# UI_measurement.net
KiCad netlist of a schematic drawn in EAGLE
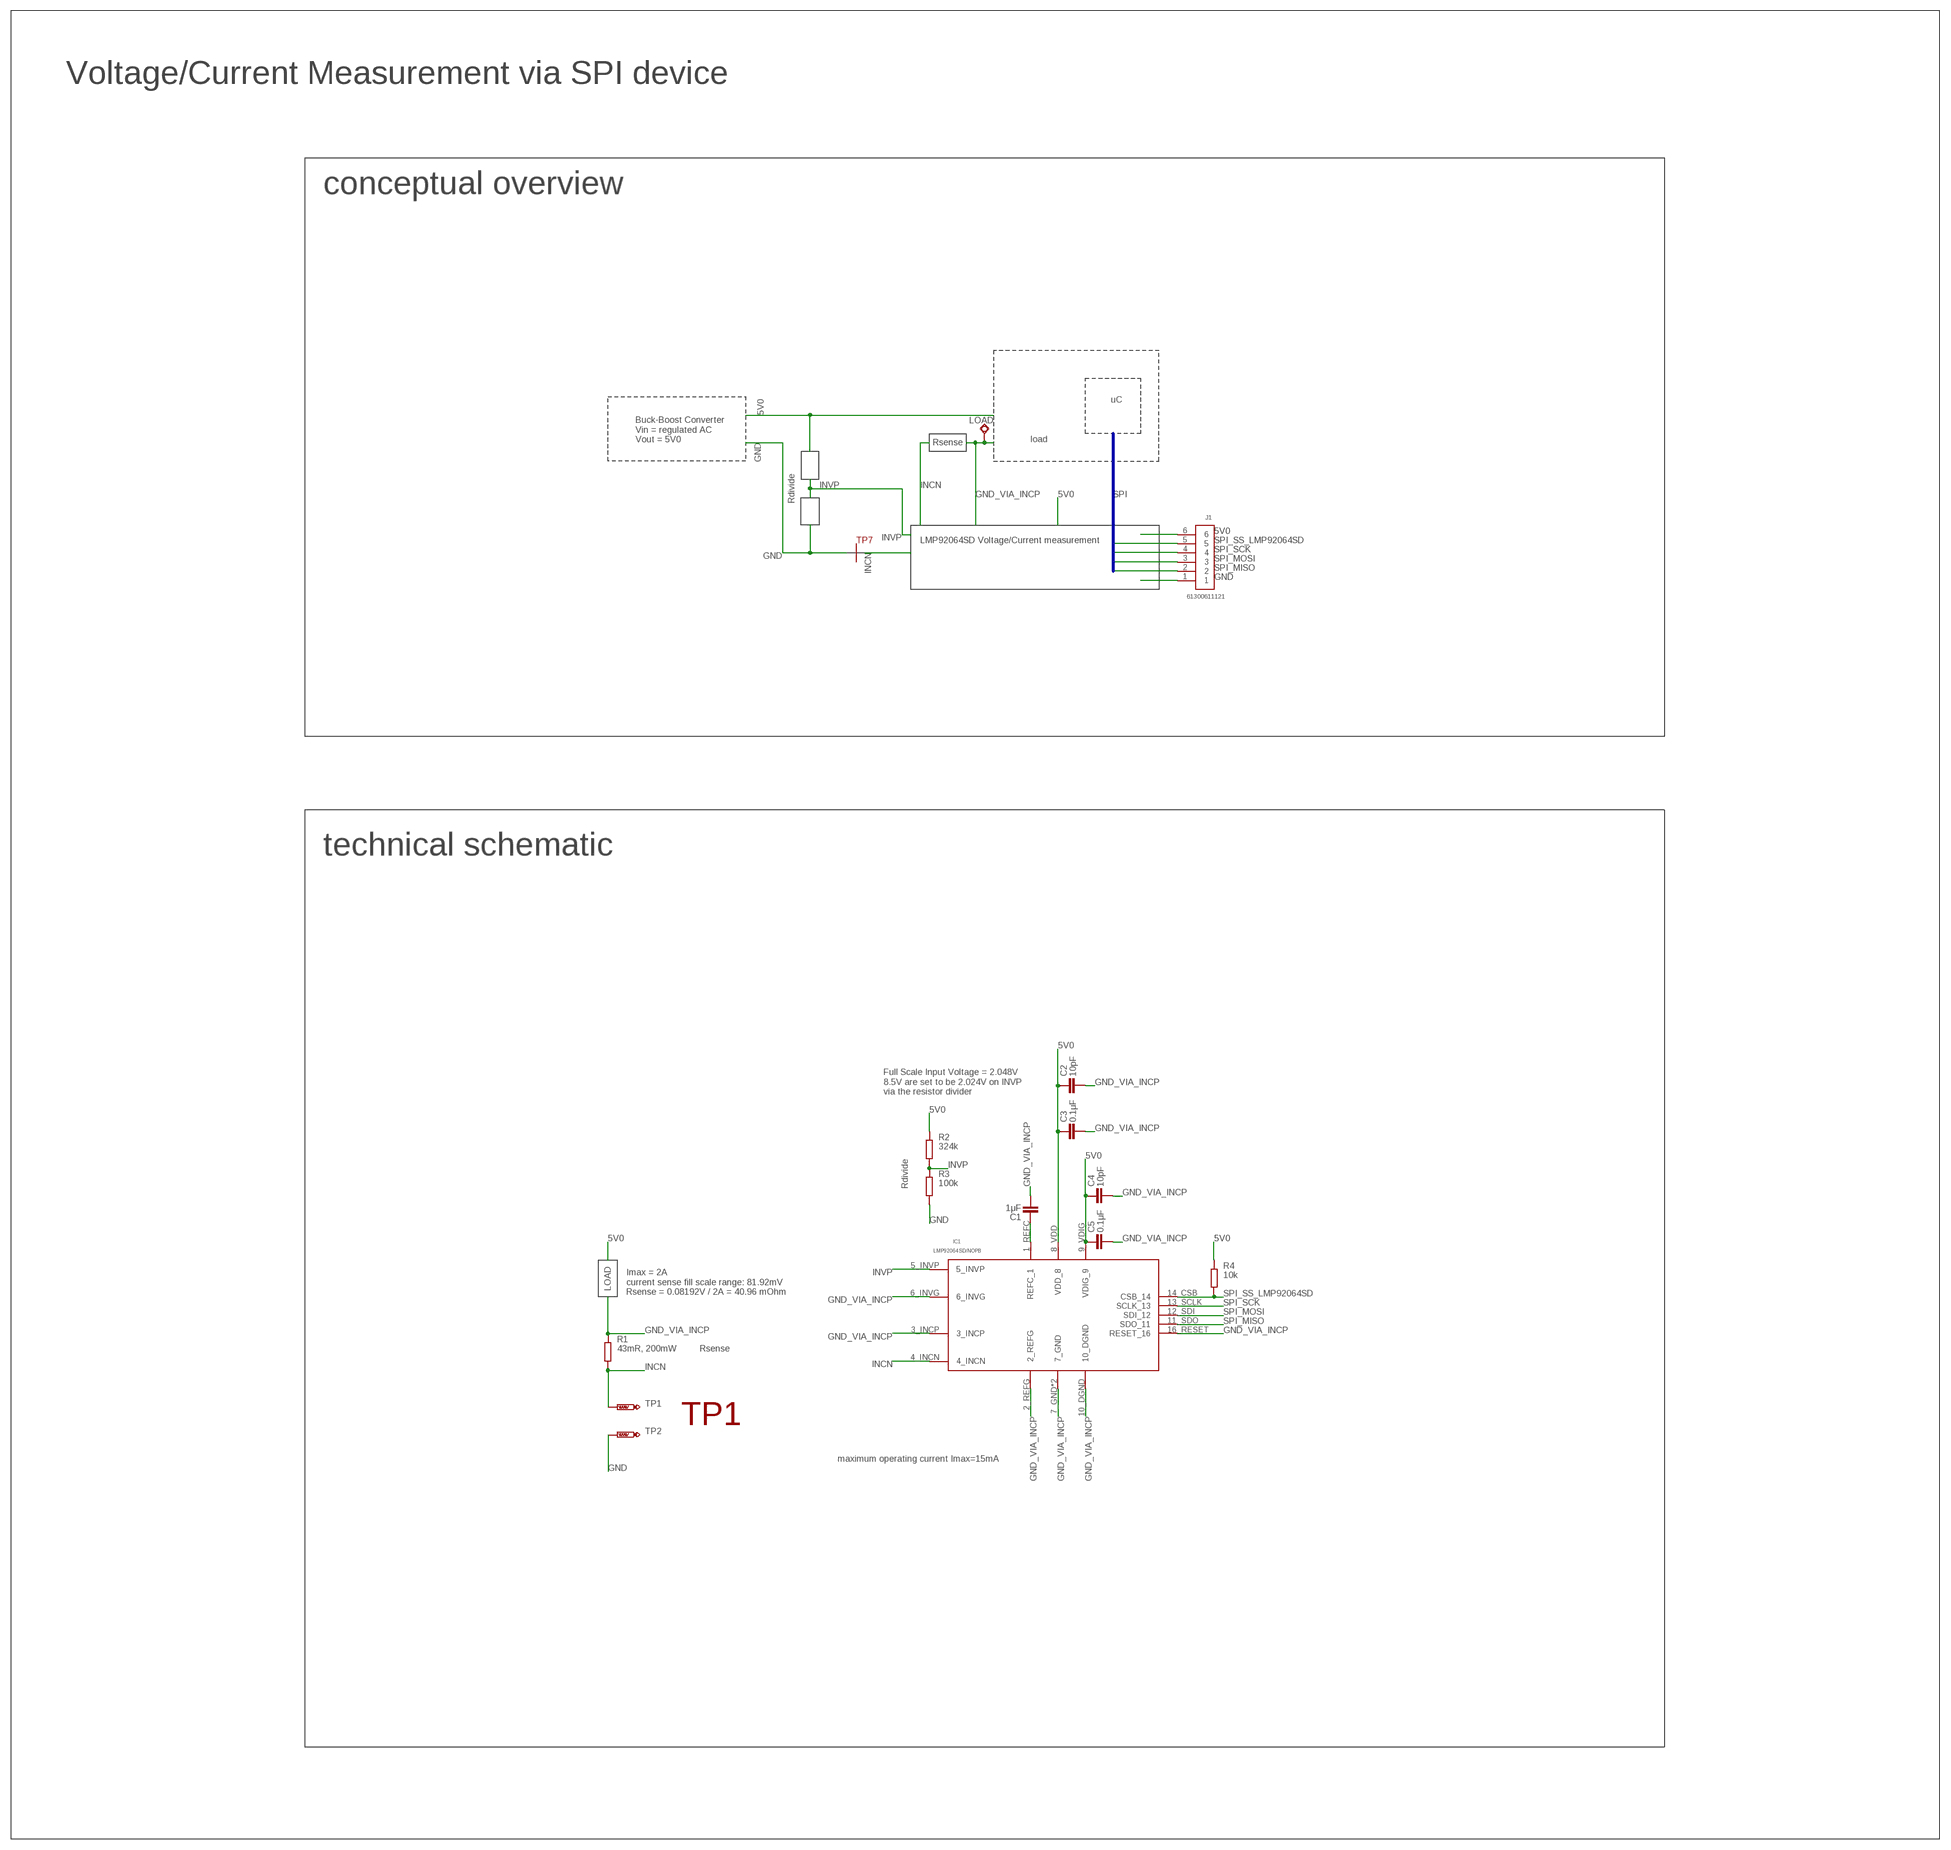
[diagram p0: schematic, sheet 1]

(export (version "E")
  (design (tool "Eeschema 10.0.6"))
  (components
    (comp (ref "C1")
      (value "1μF")
      (footprint "eagle-import:C0402")
      (libsource (lib "eagle-import") (part "C-EUC0402"))
    )
    (comp (ref "C2")
      (value "10pF")
      (footprint "eagle-import:C0402")
      (libsource (lib "eagle-import") (part "C-EUC0402"))
    )
    (comp (ref "C3")
      (value "0.1μF")
      (footprint "eagle-import:C0402")
      (libsource (lib "eagle-import") (part "C-EUC0402"))
    )
    (comp (ref "C4")
      (value "10pF")
      (footprint "eagle-import:C0402")
      (libsource (lib "eagle-import") (part "C-EUC0402"))
    )
    (comp (ref "C5")
      (value "0.1μF")
      (footprint "eagle-import:C0402")
      (libsource (lib "eagle-import") (part "C-EUC0402"))
    )
    (comp (ref "IC1")
      (value "LMP92064SD/NOPB")
      (footprint "eagle-import:WSON-16")
      (libsource (lib "eagle-import") (part "LMP92064SD"))
    )
    (comp (ref "J1")
      (value "61300611121")
      (footprint "eagle-import:61300611121")
      (fields
        (field (name "DIGI_KEY_PART_NUMBER") "732-5319-ND")
        (field (name "MANUFACTURER") "Wurth Electronics Inc.")
        (field (name "CREATED_BY") "PCBLayout.com")
      )
      (libsource (lib "eagle-import") (part "61300611121"))
    )
    (comp (ref "LOAD")
      (value "TPSQPAD1-13")
      (footprint "eagle-import:P1-13")
      (libsource (lib "eagle-import") (part "TPSQPAD1-13"))
    )
    (comp (ref "R1")
      (value "43mR, 200mW")
      (footprint "eagle-import:R2512")
      (libsource (lib "eagle-import") (part "R-EU_R2512"))
    )
    (comp (ref "R2")
      (value "324k")
      (footprint "eagle-import:R0402")
      (libsource (lib "eagle-import") (part "R-EU_R0402"))
    )
    (comp (ref "R3")
      (value "100k")
      (footprint "eagle-import:R0402")
      (libsource (lib "eagle-import") (part "R-EU_R0402"))
    )
    (comp (ref "R4")
      (value "10k")
      (footprint "eagle-import:R0402")
      (libsource (lib "eagle-import") (part "R-EU_R0402"))
    )
    (comp (ref "TP1")
      (value "PTR1TP10SQ")
      (footprint "eagle-import:TP10SQ")
      (libsource (lib "eagle-import") (part "PTR1TP10SQ"))
    )
    (comp (ref "TP2")
      (value "PTR1TP10SQ")
      (footprint "eagle-import:TP10SQ")
      (libsource (lib "eagle-import") (part "PTR1TP10SQ"))
    )
  )
  (nets
    (net (code "1") (name "/5V0") (class "Default")
      (node (ref "C2") (pin "1") (pinfunction "1_1") (pintype "passive"))
      (node (ref "C3") (pin "1") (pinfunction "1_1") (pintype "passive"))
      (node (ref "C4") (pin "1") (pinfunction "1_1") (pintype "passive"))
      (node (ref "C5") (pin "1") (pinfunction "1_1") (pintype "passive"))
      (node (ref "IC1") (pin "8_VDD") (pinfunction "VDD_8_8_VDD") (pintype "power_in"))
      (node (ref "IC1") (pin "9_VDIG") (pinfunction "VDIG_9_9_VDIG") (pintype "power_in"))
      (node (ref "J1") (pin "6") (pinfunction "6_6") (pintype "passive"))
      (node (ref "R2") (pin "2") (pinfunction "2_2") (pintype "passive"))
      (node (ref "R4") (pin "2") (pinfunction "2_2") (pintype "passive"))
    )
    (net (code "2") (name "/GND") (class "Default")
      (node (ref "J1") (pin "1") (pinfunction "1_1") (pintype "passive"))
      (node (ref "R3") (pin "1") (pinfunction "1_1") (pintype "passive"))
      (node (ref "TP2") (pin "TP") (pinfunction "TP_TP") (pintype "input"))
    )
    (net (code "3") (name "/GND_VIA_INCP") (class "Default")
      (node (ref "C1") (pin "2") (pinfunction "2_2") (pintype "passive"))
      (node (ref "C2") (pin "2") (pinfunction "2_2") (pintype "passive"))
      (node (ref "C3") (pin "2") (pinfunction "2_2") (pintype "passive"))
      (node (ref "C4") (pin "2") (pinfunction "2_2") (pintype "passive"))
      (node (ref "C5") (pin "2") (pinfunction "2_2") (pintype "passive"))
      (node (ref "IC1") (pin "10_DGND") (pinfunction "10_DGND_10_DGND") (pintype "power_in"))
      (node (ref "IC1") (pin "16_RESET") (pinfunction "RESET_16_16_RESET") (pintype "input"))
      (node (ref "IC1") (pin "2_REFG") (pinfunction "2_REFG_2_REFG") (pintype "power_in"))
      (node (ref "IC1") (pin "3_INCP") (pinfunction "3_INCP_3_INCP") (pintype "input"))
      (node (ref "IC1") (pin "6_INVG") (pinfunction "6_INVG_6_INVG") (pintype "output"))
      (node (ref "IC1") (pin "7_GND") (pinfunction "7_GND_7_GND") (pintype "power_in"))
      (node (ref "IC1") (pin "GND1") (pinfunction "7_GND_GND1") (pintype "power_in"))
      (node (ref "LOAD") (pin "TP") (pinfunction "TP_TP") (pintype "input"))
      (node (ref "R1") (pin "2") (pinfunction "2_2") (pintype "passive"))
    )
    (net (code "4") (name "/INCN") (class "Default")
      (node (ref "IC1") (pin "4_INCN") (pinfunction "4_INCN_4_INCN") (pintype "output"))
      (node (ref "R1") (pin "1") (pinfunction "1_1") (pintype "passive"))
      (node (ref "TP1") (pin "TP") (pinfunction "TP_TP") (pintype "input"))
    )
    (net (code "5") (name "/INVP") (class "Default")
      (node (ref "IC1") (pin "5_INVP") (pinfunction "5_INVP_5_INVP") (pintype "input"))
      (node (ref "R2") (pin "1") (pinfunction "1_1") (pintype "passive"))
      (node (ref "R3") (pin "2") (pinfunction "2_2") (pintype "passive"))
    )
    (net (code "6") (name "/SPI_MISO") (class "Default")
      (node (ref "IC1") (pin "11_SDO") (pinfunction "SDO_11_11_SDO") (pintype "output"))
      (node (ref "J1") (pin "2") (pinfunction "2_2") (pintype "passive"))
    )
    (net (code "7") (name "/SPI_MOSI") (class "Default")
      (node (ref "IC1") (pin "12_SDI") (pinfunction "SDI_12_12_SDI") (pintype "input"))
      (node (ref "J1") (pin "3") (pinfunction "3_3") (pintype "passive"))
    )
    (net (code "8") (name "/SPI_SCK") (class "Default")
      (node (ref "IC1") (pin "13_SCLK") (pinfunction "SCLK_13_13_SCLK") (pintype "input"))
      (node (ref "J1") (pin "4") (pinfunction "4_4") (pintype "passive"))
    )
    (net (code "9") (name "/SPI_SS_LMP92064SD") (class "Default")
      (node (ref "IC1") (pin "14_CSB") (pinfunction "CSB_14_14_CSB") (pintype "bidirectional"))
      (node (ref "J1") (pin "5") (pinfunction "5_5") (pintype "passive"))
      (node (ref "R4") (pin "1") (pinfunction "1_1") (pintype "passive"))
    )
    (net (code "10") (name "Net-(IC1-REFC_1)") (class "Default")
      (node (ref "C1") (pin "1") (pinfunction "1_1") (pintype "passive"))
      (node (ref "IC1") (pin "1_REFC") (pinfunction "REFC_1_1_REFC") (pintype "bidirectional"))
    )
  )
)
